# BIT_1.net
KiCad netlist of a schematic drawn in EasyEDA
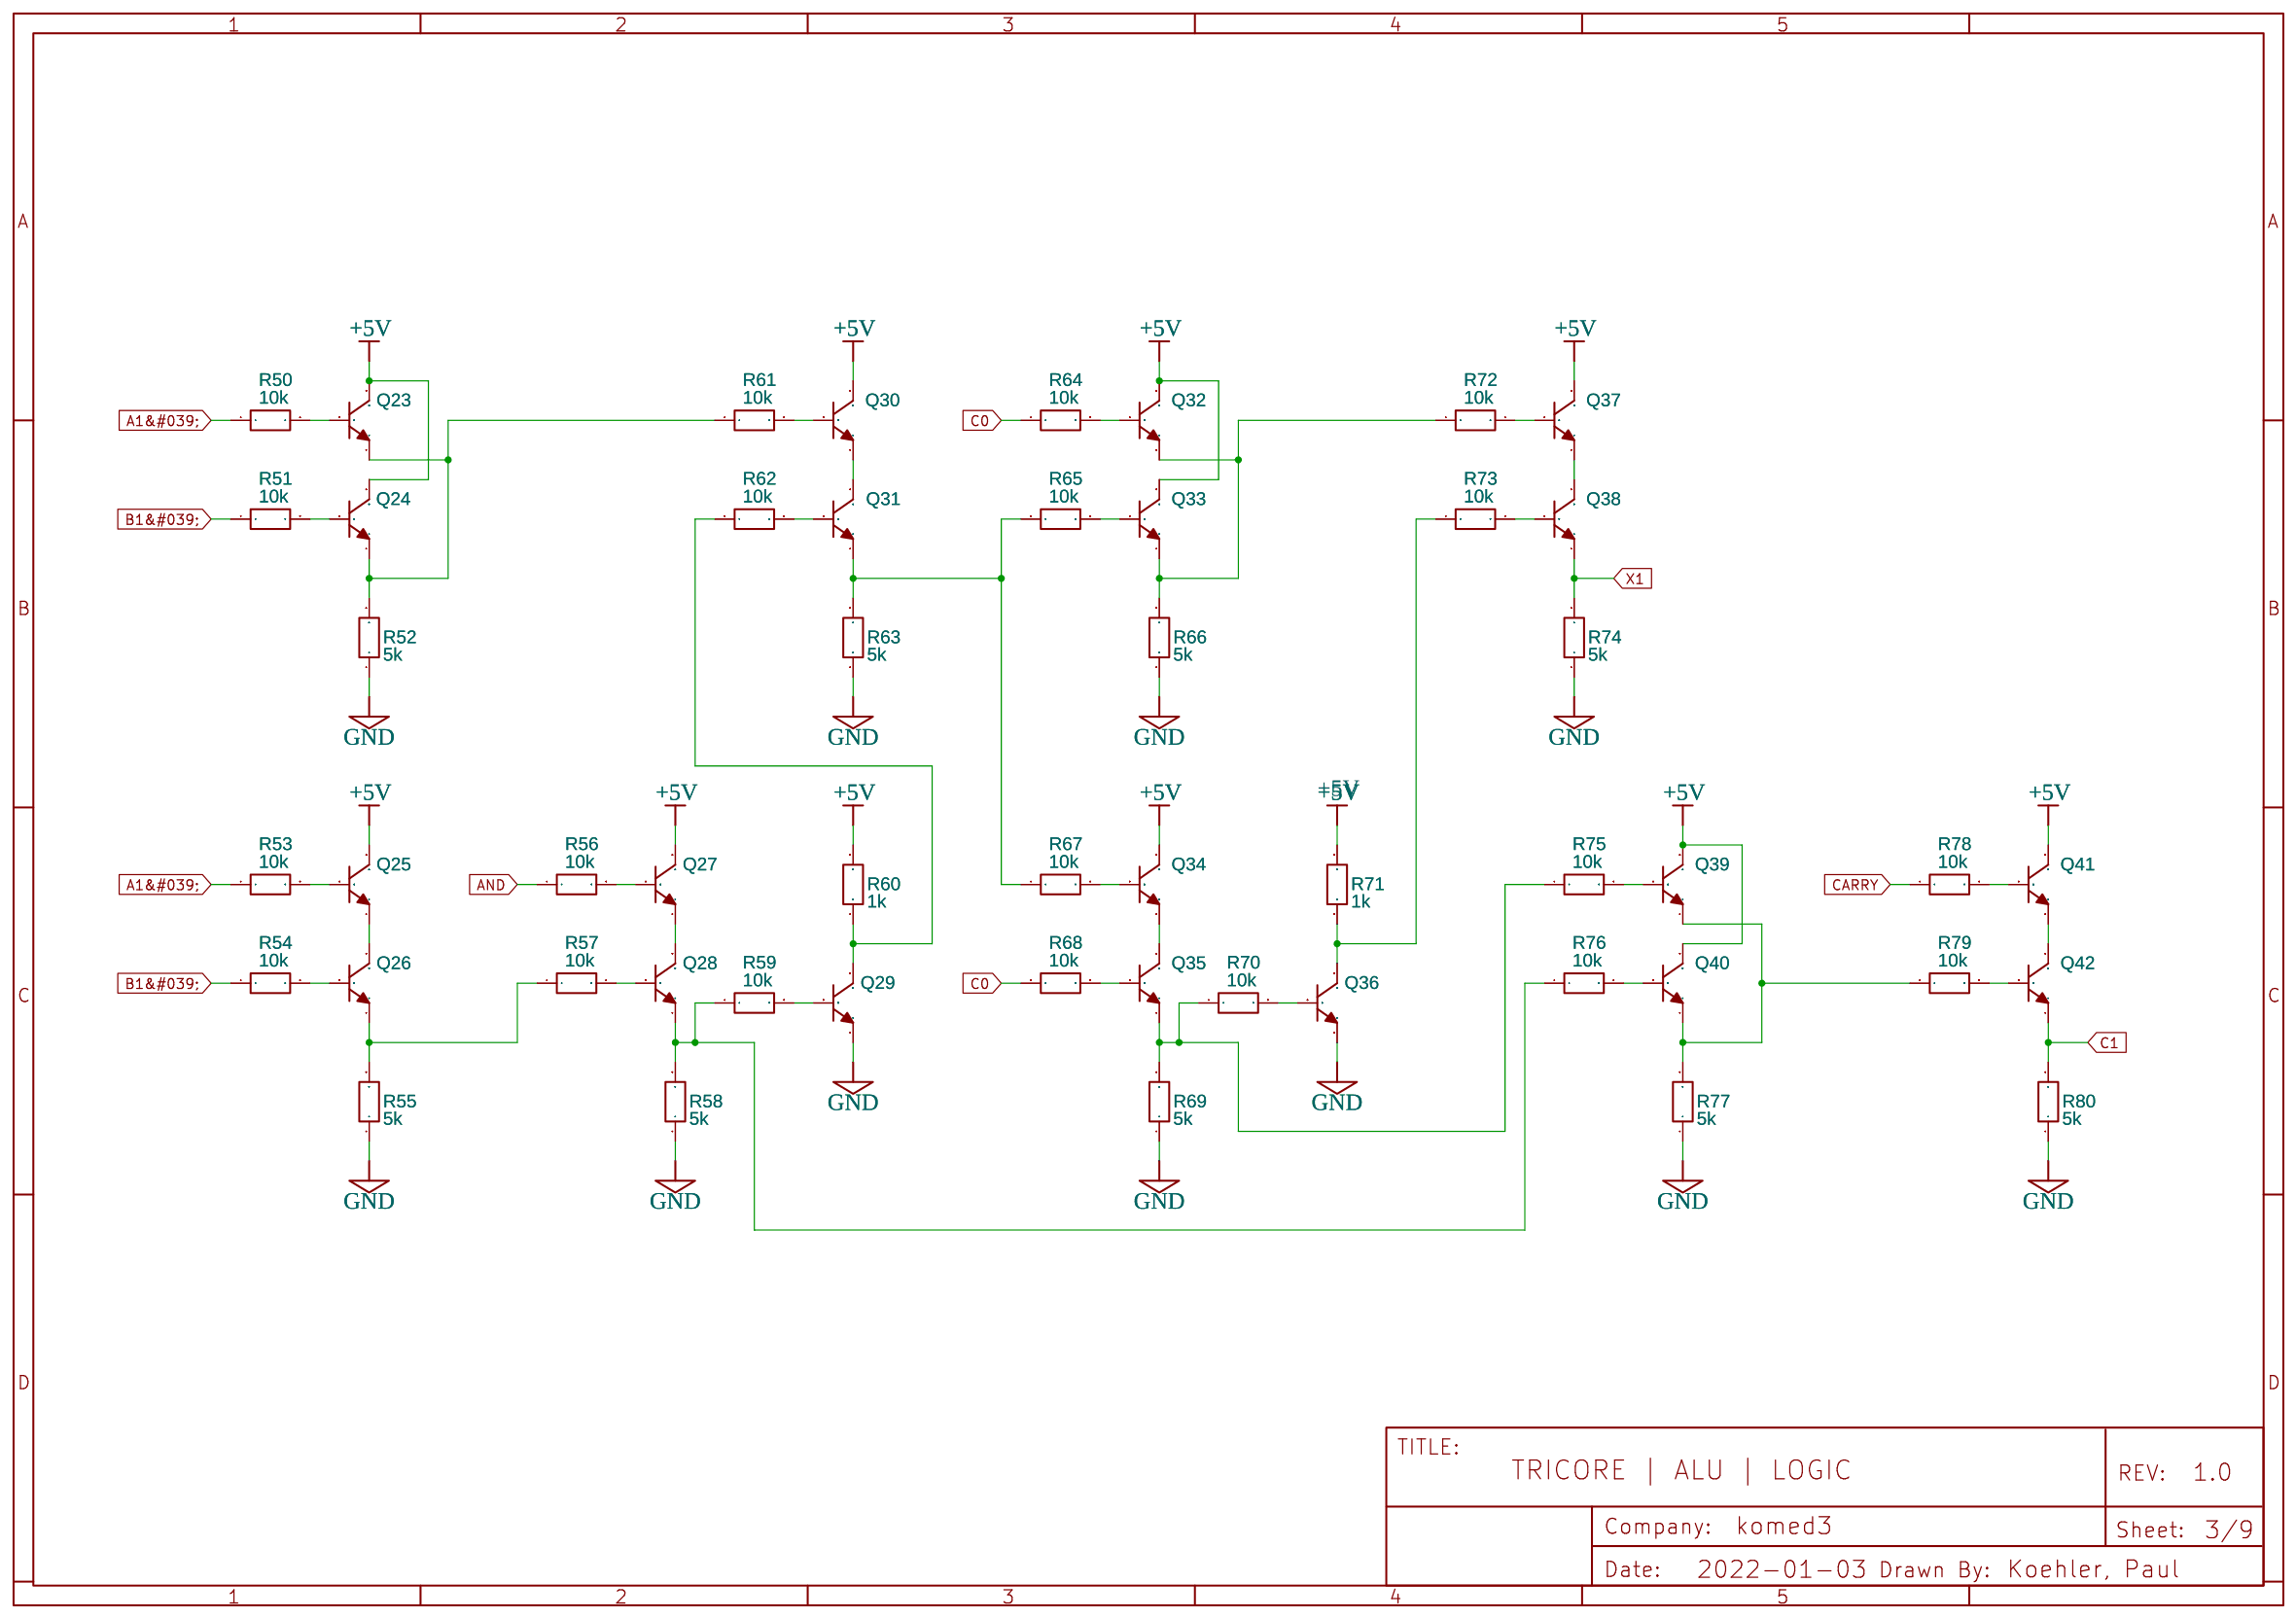
[diagram p0: schematic sheet]

(export (version "E")
  (design (tool "Eeschema 10.0.6"))
  (components
    (comp (ref "Q23")
      (value "2N3904(TO-92)")
      (fields (field (name "BOM_Manufacturer Part") "2N3904") (field (name "BOM_Supplier Part") "C118538"))
      (libsource (lib "") (part "2N3904(TO-92)"))
    )
    (comp (ref "Q24")
      (value "2N3904(TO-92)")
      (fields (field (name "BOM_Manufacturer Part") "2N3904") (field (name "BOM_Supplier Part") "C118538"))
      (libsource (lib "") (part "2N3904(TO-92)"))
    )
    (comp (ref "Q25")
      (value "2N3904(TO-92)")
      (fields (field (name "BOM_Manufacturer Part") "2N3904") (field (name "BOM_Supplier Part") "C118538"))
      (libsource (lib "") (part "2N3904(TO-92)"))
    )
    (comp (ref "Q26")
      (value "2N3904(TO-92)")
      (fields (field (name "BOM_Manufacturer Part") "2N3904") (field (name "BOM_Supplier Part") "C118538"))
      (libsource (lib "") (part "2N3904(TO-92)"))
    )
    (comp (ref "Q27")
      (value "2N3904(TO-92)")
      (fields (field (name "BOM_Manufacturer Part") "2N3904") (field (name "BOM_Supplier Part") "C118538"))
      (libsource (lib "") (part "2N3904(TO-92)"))
    )
    (comp (ref "Q28")
      (value "2N3904(TO-92)")
      (fields (field (name "BOM_Manufacturer Part") "2N3904") (field (name "BOM_Supplier Part") "C118538"))
      (libsource (lib "") (part "2N3904(TO-92)"))
    )
    (comp (ref "Q29")
      (value "2N3904(TO-92)")
      (fields (field (name "BOM_Manufacturer Part") "2N3904") (field (name "BOM_Supplier Part") "C118538"))
      (libsource (lib "") (part "2N3904(TO-92)"))
    )
    (comp (ref "Q30")
      (value "2N3904(TO-92)")
      (fields (field (name "BOM_Manufacturer Part") "2N3904") (field (name "BOM_Supplier Part") "C118538"))
      (libsource (lib "") (part "2N3904(TO-92)"))
    )
    (comp (ref "Q31")
      (value "2N3904(TO-92)")
      (fields (field (name "BOM_Manufacturer Part") "2N3904") (field (name "BOM_Supplier Part") "C118538"))
      (libsource (lib "") (part "2N3904(TO-92)"))
    )
    (comp (ref "Q32")
      (value "2N3904(TO-92)")
      (fields (field (name "BOM_Manufacturer Part") "2N3904") (field (name "BOM_Supplier Part") "C118538"))
      (libsource (lib "") (part "2N3904(TO-92)"))
    )
    (comp (ref "Q33")
      (value "2N3904(TO-92)")
      (fields (field (name "BOM_Manufacturer Part") "2N3904") (field (name "BOM_Supplier Part") "C118538"))
      (libsource (lib "") (part "2N3904(TO-92)"))
    )
    (comp (ref "Q34")
      (value "2N3904(TO-92)")
      (fields (field (name "BOM_Manufacturer Part") "2N3904") (field (name "BOM_Supplier Part") "C118538"))
      (libsource (lib "") (part "2N3904(TO-92)"))
    )
    (comp (ref "Q35")
      (value "2N3904(TO-92)")
      (fields (field (name "BOM_Manufacturer Part") "2N3904") (field (name "BOM_Supplier Part") "C118538"))
      (libsource (lib "") (part "2N3904(TO-92)"))
    )
    (comp (ref "Q36")
      (value "2N3904(TO-92)")
      (fields (field (name "BOM_Manufacturer Part") "2N3904") (field (name "BOM_Supplier Part") "C118538"))
      (libsource (lib "") (part "2N3904(TO-92)"))
    )
    (comp (ref "Q37")
      (value "2N3904(TO-92)")
      (fields (field (name "BOM_Manufacturer Part") "2N3904") (field (name "BOM_Supplier Part") "C118538"))
      (libsource (lib "") (part "2N3904(TO-92)"))
    )
    (comp (ref "Q38")
      (value "2N3904(TO-92)")
      (fields (field (name "BOM_Manufacturer Part") "2N3904") (field (name "BOM_Supplier Part") "C118538"))
      (libsource (lib "") (part "2N3904(TO-92)"))
    )
    (comp (ref "Q39")
      (value "2N3904(TO-92)")
      (fields (field (name "BOM_Manufacturer Part") "2N3904") (field (name "BOM_Supplier Part") "C118538"))
      (libsource (lib "") (part "2N3904(TO-92)"))
    )
    (comp (ref "Q40")
      (value "2N3904(TO-92)")
      (fields (field (name "BOM_Manufacturer Part") "2N3904") (field (name "BOM_Supplier Part") "C118538"))
      (libsource (lib "") (part "2N3904(TO-92)"))
    )
    (comp (ref "Q41")
      (value "2N3904(TO-92)")
      (fields (field (name "BOM_Manufacturer Part") "2N3904") (field (name "BOM_Supplier Part") "C118538"))
      (libsource (lib "") (part "2N3904(TO-92)"))
    )
    (comp (ref "Q42")
      (value "2N3904(TO-92)")
      (fields (field (name "BOM_Manufacturer Part") "2N3904") (field (name "BOM_Supplier Part") "C118538"))
      (libsource (lib "") (part "2N3904(TO-92)"))
    )
    (comp (ref "R50") (value "10k") (libsource (lib "") (part "R_AXIAL-0.3_EU")))
    (comp (ref "R51") (value "10k") (libsource (lib "") (part "R_AXIAL-0.3_EU")))
    (comp (ref "R52") (value "5k") (libsource (lib "") (part "R_AXIAL-0.3_EU_1")))
    (comp (ref "R53") (value "10k") (libsource (lib "") (part "R_AXIAL-0.3_EU")))
    (comp (ref "R54") (value "10k") (libsource (lib "") (part "R_AXIAL-0.3_EU")))
    (comp (ref "R55") (value "5k") (libsource (lib "") (part "R_AXIAL-0.3_EU_1")))
    (comp (ref "R56") (value "10k") (libsource (lib "") (part "R_AXIAL-0.3_EU")))
    (comp (ref "R57") (value "10k") (libsource (lib "") (part "R_AXIAL-0.3_EU")))
    (comp (ref "R58") (value "5k") (libsource (lib "") (part "R_AXIAL-0.3_EU_1")))
    (comp (ref "R59") (value "10k") (libsource (lib "") (part "R_AXIAL-0.3_EU")))
    (comp (ref "R60") (value "1k") (libsource (lib "") (part "R_AXIAL-0.3_EU_1")))
    (comp (ref "R61") (value "10k") (libsource (lib "") (part "R_AXIAL-0.3_EU")))
    (comp (ref "R62") (value "10k") (libsource (lib "") (part "R_AXIAL-0.3_EU")))
    (comp (ref "R63") (value "5k") (libsource (lib "") (part "R_AXIAL-0.3_EU_1")))
    (comp (ref "R64") (value "10k") (libsource (lib "") (part "R_AXIAL-0.3_EU")))
    (comp (ref "R65") (value "10k") (libsource (lib "") (part "R_AXIAL-0.3_EU")))
    (comp (ref "R66") (value "5k") (libsource (lib "") (part "R_AXIAL-0.3_EU_1")))
    (comp (ref "R67") (value "10k") (libsource (lib "") (part "R_AXIAL-0.3_EU")))
    (comp (ref "R68") (value "10k") (libsource (lib "") (part "R_AXIAL-0.3_EU")))
    (comp (ref "R69") (value "5k") (libsource (lib "") (part "R_AXIAL-0.3_EU_1")))
    (comp (ref "R70") (value "10k") (libsource (lib "") (part "R_AXIAL-0.3_EU")))
    (comp (ref "R71") (value "1k") (libsource (lib "") (part "R_AXIAL-0.3_EU_1")))
    (comp (ref "R72") (value "10k") (libsource (lib "") (part "R_AXIAL-0.3_EU")))
    (comp (ref "R73") (value "10k") (libsource (lib "") (part "R_AXIAL-0.3_EU")))
    (comp (ref "R74") (value "5k") (libsource (lib "") (part "R_AXIAL-0.3_EU_1")))
    (comp (ref "R75") (value "10k") (libsource (lib "") (part "R_AXIAL-0.3_EU")))
    (comp (ref "R76") (value "10k") (libsource (lib "") (part "R_AXIAL-0.3_EU")))
    (comp (ref "R77") (value "5k") (libsource (lib "") (part "R_AXIAL-0.3_EU_1")))
    (comp (ref "R78") (value "10k") (libsource (lib "") (part "R_AXIAL-0.3_EU")))
    (comp (ref "R79") (value "10k") (libsource (lib "") (part "R_AXIAL-0.3_EU")))
    (comp (ref "R80") (value "5k") (libsource (lib "") (part "R_AXIAL-0.3_EU_1")))
  )
  (nets
    (net (code "1") (name "+5V") (class "Default")
      (node (ref "Q23") (pin "3") (pinfunction "C_3") (pintype "unspecified"))
      (node (ref "Q24") (pin "3") (pinfunction "C_3") (pintype "unspecified"))
      (node (ref "Q25") (pin "3") (pinfunction "C_3") (pintype "unspecified"))
      (node (ref "Q27") (pin "3") (pinfunction "C_3") (pintype "unspecified"))
      (node (ref "Q30") (pin "3") (pinfunction "C_3") (pintype "unspecified"))
      (node (ref "Q32") (pin "3") (pinfunction "C_3") (pintype "unspecified"))
      (node (ref "Q33") (pin "3") (pinfunction "C_3") (pintype "unspecified"))
      (node (ref "Q34") (pin "3") (pinfunction "C_3") (pintype "unspecified"))
      (node (ref "Q37") (pin "3") (pinfunction "C_3") (pintype "unspecified"))
      (node (ref "Q39") (pin "3") (pinfunction "C_3") (pintype "unspecified"))
      (node (ref "Q40") (pin "3") (pinfunction "C_3") (pintype "unspecified"))
      (node (ref "Q41") (pin "3") (pinfunction "C_3") (pintype "unspecified"))
      (node (ref "R60") (pin "2") (pinfunction "2_2") (pintype "unspecified"))
      (node (ref "R71") (pin "2") (pinfunction "2_2") (pintype "unspecified"))
    )
    (net (code "2") (name "A1&#039;") (class "Default")
      (node (ref "R50") (pin "1") (pinfunction "1_1") (pintype "unspecified"))
      (node (ref "R53") (pin "1") (pinfunction "1_1") (pintype "unspecified"))
    )
    (net (code "3") (name "AND") (class "Default")
      (node (ref "R56") (pin "1") (pinfunction "1_1") (pintype "unspecified"))
    )
    (net (code "4") (name "B1&#039;") (class "Default")
      (node (ref "R51") (pin "1") (pinfunction "1_1") (pintype "unspecified"))
      (node (ref "R54") (pin "1") (pinfunction "1_1") (pintype "unspecified"))
    )
    (net (code "5") (name "C0") (class "Default")
      (node (ref "R64") (pin "1") (pinfunction "1_1") (pintype "unspecified"))
      (node (ref "R68") (pin "1") (pinfunction "1_1") (pintype "unspecified"))
    )
    (net (code "6") (name "C1") (class "Default")
      (node (ref "Q42") (pin "1") (pinfunction "E_1") (pintype "unspecified"))
      (node (ref "R80") (pin "2") (pinfunction "2_2") (pintype "unspecified"))
    )
    (net (code "7") (name "CARRY") (class "Default")
      (node (ref "R78") (pin "1") (pinfunction "1_1") (pintype "unspecified"))
    )
    (net (code "8") (name "GND") (class "Default")
      (node (ref "Q29") (pin "1") (pinfunction "E_1") (pintype "unspecified"))
      (node (ref "Q36") (pin "1") (pinfunction "E_1") (pintype "unspecified"))
      (node (ref "R52") (pin "1") (pinfunction "1_1") (pintype "unspecified"))
      (node (ref "R55") (pin "1") (pinfunction "1_1") (pintype "unspecified"))
      (node (ref "R58") (pin "1") (pinfunction "1_1") (pintype "unspecified"))
      (node (ref "R63") (pin "1") (pinfunction "1_1") (pintype "unspecified"))
      (node (ref "R66") (pin "1") (pinfunction "1_1") (pintype "unspecified"))
      (node (ref "R69") (pin "1") (pinfunction "1_1") (pintype "unspecified"))
      (node (ref "R74") (pin "1") (pinfunction "1_1") (pintype "unspecified"))
      (node (ref "R77") (pin "1") (pinfunction "1_1") (pintype "unspecified"))
      (node (ref "R80") (pin "1") (pinfunction "1_1") (pintype "unspecified"))
    )
    (net (code "9") (name "Net-(Q23-B)") (class "Default")
      (node (ref "Q23") (pin "2") (pinfunction "B_2") (pintype "unspecified"))
      (node (ref "R50") (pin "2") (pinfunction "2_2") (pintype "unspecified"))
    )
    (net (code "10") (name "Net-(Q23-E)") (class "Default")
      (node (ref "Q23") (pin "1") (pinfunction "E_1") (pintype "unspecified"))
      (node (ref "Q24") (pin "1") (pinfunction "E_1") (pintype "unspecified"))
      (node (ref "R52") (pin "2") (pinfunction "2_2") (pintype "unspecified"))
      (node (ref "R61") (pin "1") (pinfunction "1_1") (pintype "unspecified"))
    )
    (net (code "11") (name "Net-(Q24-B)") (class "Default")
      (node (ref "Q24") (pin "2") (pinfunction "B_2") (pintype "unspecified"))
      (node (ref "R51") (pin "2") (pinfunction "2_2") (pintype "unspecified"))
    )
    (net (code "12") (name "Net-(Q25-B)") (class "Default")
      (node (ref "Q25") (pin "2") (pinfunction "B_2") (pintype "unspecified"))
      (node (ref "R53") (pin "2") (pinfunction "2_2") (pintype "unspecified"))
    )
    (net (code "13") (name "Net-(Q25-E)") (class "Default")
      (node (ref "Q25") (pin "1") (pinfunction "E_1") (pintype "unspecified"))
      (node (ref "Q26") (pin "3") (pinfunction "C_3") (pintype "unspecified"))
    )
    (net (code "14") (name "Net-(Q26-B)") (class "Default")
      (node (ref "Q26") (pin "2") (pinfunction "B_2") (pintype "unspecified"))
      (node (ref "R54") (pin "2") (pinfunction "2_2") (pintype "unspecified"))
    )
    (net (code "15") (name "Net-(Q26-E)") (class "Default")
      (node (ref "Q26") (pin "1") (pinfunction "E_1") (pintype "unspecified"))
      (node (ref "R55") (pin "2") (pinfunction "2_2") (pintype "unspecified"))
      (node (ref "R57") (pin "1") (pinfunction "1_1") (pintype "unspecified"))
    )
    (net (code "16") (name "Net-(Q27-B)") (class "Default")
      (node (ref "Q27") (pin "2") (pinfunction "B_2") (pintype "unspecified"))
      (node (ref "R56") (pin "2") (pinfunction "2_2") (pintype "unspecified"))
    )
    (net (code "17") (name "Net-(Q27-E)") (class "Default")
      (node (ref "Q27") (pin "1") (pinfunction "E_1") (pintype "unspecified"))
      (node (ref "Q28") (pin "3") (pinfunction "C_3") (pintype "unspecified"))
    )
    (net (code "18") (name "Net-(Q28-B)") (class "Default")
      (node (ref "Q28") (pin "2") (pinfunction "B_2") (pintype "unspecified"))
      (node (ref "R57") (pin "2") (pinfunction "2_2") (pintype "unspecified"))
    )
    (net (code "19") (name "Net-(Q28-E)") (class "Default")
      (node (ref "Q28") (pin "1") (pinfunction "E_1") (pintype "unspecified"))
      (node (ref "R58") (pin "2") (pinfunction "2_2") (pintype "unspecified"))
      (node (ref "R59") (pin "1") (pinfunction "1_1") (pintype "unspecified"))
      (node (ref "R76") (pin "1") (pinfunction "1_1") (pintype "unspecified"))
    )
    (net (code "20") (name "Net-(Q29-B)") (class "Default")
      (node (ref "Q29") (pin "2") (pinfunction "B_2") (pintype "unspecified"))
      (node (ref "R59") (pin "2") (pinfunction "2_2") (pintype "unspecified"))
    )
    (net (code "21") (name "Net-(Q29-C)") (class "Default")
      (node (ref "Q29") (pin "3") (pinfunction "C_3") (pintype "unspecified"))
      (node (ref "R60") (pin "1") (pinfunction "1_1") (pintype "unspecified"))
      (node (ref "R62") (pin "1") (pinfunction "1_1") (pintype "unspecified"))
    )
    (net (code "22") (name "Net-(Q30-B)") (class "Default")
      (node (ref "Q30") (pin "2") (pinfunction "B_2") (pintype "unspecified"))
      (node (ref "R61") (pin "2") (pinfunction "2_2") (pintype "unspecified"))
    )
    (net (code "23") (name "Net-(Q30-E)") (class "Default")
      (node (ref "Q30") (pin "1") (pinfunction "E_1") (pintype "unspecified"))
      (node (ref "Q31") (pin "3") (pinfunction "C_3") (pintype "unspecified"))
    )
    (net (code "24") (name "Net-(Q31-B)") (class "Default")
      (node (ref "Q31") (pin "2") (pinfunction "B_2") (pintype "unspecified"))
      (node (ref "R62") (pin "2") (pinfunction "2_2") (pintype "unspecified"))
    )
    (net (code "25") (name "Net-(Q31-E)") (class "Default")
      (node (ref "Q31") (pin "1") (pinfunction "E_1") (pintype "unspecified"))
      (node (ref "R63") (pin "2") (pinfunction "2_2") (pintype "unspecified"))
      (node (ref "R65") (pin "1") (pinfunction "1_1") (pintype "unspecified"))
      (node (ref "R67") (pin "1") (pinfunction "1_1") (pintype "unspecified"))
    )
    (net (code "26") (name "Net-(Q32-B)") (class "Default")
      (node (ref "Q32") (pin "2") (pinfunction "B_2") (pintype "unspecified"))
      (node (ref "R64") (pin "2") (pinfunction "2_2") (pintype "unspecified"))
    )
    (net (code "27") (name "Net-(Q32-E)") (class "Default")
      (node (ref "Q32") (pin "1") (pinfunction "E_1") (pintype "unspecified"))
      (node (ref "Q33") (pin "1") (pinfunction "E_1") (pintype "unspecified"))
      (node (ref "R66") (pin "2") (pinfunction "2_2") (pintype "unspecified"))
      (node (ref "R72") (pin "1") (pinfunction "1_1") (pintype "unspecified"))
    )
    (net (code "28") (name "Net-(Q33-B)") (class "Default")
      (node (ref "Q33") (pin "2") (pinfunction "B_2") (pintype "unspecified"))
      (node (ref "R65") (pin "2") (pinfunction "2_2") (pintype "unspecified"))
    )
    (net (code "29") (name "Net-(Q34-B)") (class "Default")
      (node (ref "Q34") (pin "2") (pinfunction "B_2") (pintype "unspecified"))
      (node (ref "R67") (pin "2") (pinfunction "2_2") (pintype "unspecified"))
    )
    (net (code "30") (name "Net-(Q34-E)") (class "Default")
      (node (ref "Q34") (pin "1") (pinfunction "E_1") (pintype "unspecified"))
      (node (ref "Q35") (pin "3") (pinfunction "C_3") (pintype "unspecified"))
    )
    (net (code "31") (name "Net-(Q35-B)") (class "Default")
      (node (ref "Q35") (pin "2") (pinfunction "B_2") (pintype "unspecified"))
      (node (ref "R68") (pin "2") (pinfunction "2_2") (pintype "unspecified"))
    )
    (net (code "32") (name "Net-(Q35-E)") (class "Default")
      (node (ref "Q35") (pin "1") (pinfunction "E_1") (pintype "unspecified"))
      (node (ref "R69") (pin "2") (pinfunction "2_2") (pintype "unspecified"))
      (node (ref "R70") (pin "1") (pinfunction "1_1") (pintype "unspecified"))
      (node (ref "R75") (pin "1") (pinfunction "1_1") (pintype "unspecified"))
    )
    (net (code "33") (name "Net-(Q36-B)") (class "Default")
      (node (ref "Q36") (pin "2") (pinfunction "B_2") (pintype "unspecified"))
      (node (ref "R70") (pin "2") (pinfunction "2_2") (pintype "unspecified"))
    )
    (net (code "34") (name "Net-(Q36-C)") (class "Default")
      (node (ref "Q36") (pin "3") (pinfunction "C_3") (pintype "unspecified"))
      (node (ref "R71") (pin "1") (pinfunction "1_1") (pintype "unspecified"))
      (node (ref "R73") (pin "1") (pinfunction "1_1") (pintype "unspecified"))
    )
    (net (code "35") (name "Net-(Q37-B)") (class "Default")
      (node (ref "Q37") (pin "2") (pinfunction "B_2") (pintype "unspecified"))
      (node (ref "R72") (pin "2") (pinfunction "2_2") (pintype "unspecified"))
    )
    (net (code "36") (name "Net-(Q37-E)") (class "Default")
      (node (ref "Q37") (pin "1") (pinfunction "E_1") (pintype "unspecified"))
      (node (ref "Q38") (pin "3") (pinfunction "C_3") (pintype "unspecified"))
    )
    (net (code "37") (name "Net-(Q38-B)") (class "Default")
      (node (ref "Q38") (pin "2") (pinfunction "B_2") (pintype "unspecified"))
      (node (ref "R73") (pin "2") (pinfunction "2_2") (pintype "unspecified"))
    )
    (net (code "38") (name "Net-(Q39-B)") (class "Default")
      (node (ref "Q39") (pin "2") (pinfunction "B_2") (pintype "unspecified"))
      (node (ref "R75") (pin "2") (pinfunction "2_2") (pintype "unspecified"))
    )
    (net (code "39") (name "Net-(Q39-E)") (class "Default")
      (node (ref "Q39") (pin "1") (pinfunction "E_1") (pintype "unspecified"))
      (node (ref "Q40") (pin "1") (pinfunction "E_1") (pintype "unspecified"))
      (node (ref "R77") (pin "2") (pinfunction "2_2") (pintype "unspecified"))
      (node (ref "R79") (pin "1") (pinfunction "1_1") (pintype "unspecified"))
    )
    (net (code "40") (name "Net-(Q40-B)") (class "Default")
      (node (ref "Q40") (pin "2") (pinfunction "B_2") (pintype "unspecified"))
      (node (ref "R76") (pin "2") (pinfunction "2_2") (pintype "unspecified"))
    )
    (net (code "41") (name "Net-(Q41-B)") (class "Default")
      (node (ref "Q41") (pin "2") (pinfunction "B_2") (pintype "unspecified"))
      (node (ref "R78") (pin "2") (pinfunction "2_2") (pintype "unspecified"))
    )
    (net (code "42") (name "Net-(Q41-E)") (class "Default")
      (node (ref "Q41") (pin "1") (pinfunction "E_1") (pintype "unspecified"))
      (node (ref "Q42") (pin "3") (pinfunction "C_3") (pintype "unspecified"))
    )
    (net (code "43") (name "Net-(Q42-B)") (class "Default")
      (node (ref "Q42") (pin "2") (pinfunction "B_2") (pintype "unspecified"))
      (node (ref "R79") (pin "2") (pinfunction "2_2") (pintype "unspecified"))
    )
    (net (code "44") (name "X1") (class "Default")
      (node (ref "Q38") (pin "1") (pinfunction "E_1") (pintype "unspecified"))
      (node (ref "R74") (pin "2") (pinfunction "2_2") (pintype "unspecified"))
    )
  )
)
